# RS485.net
KiCad netlist of a schematic drawn in Altium Designer
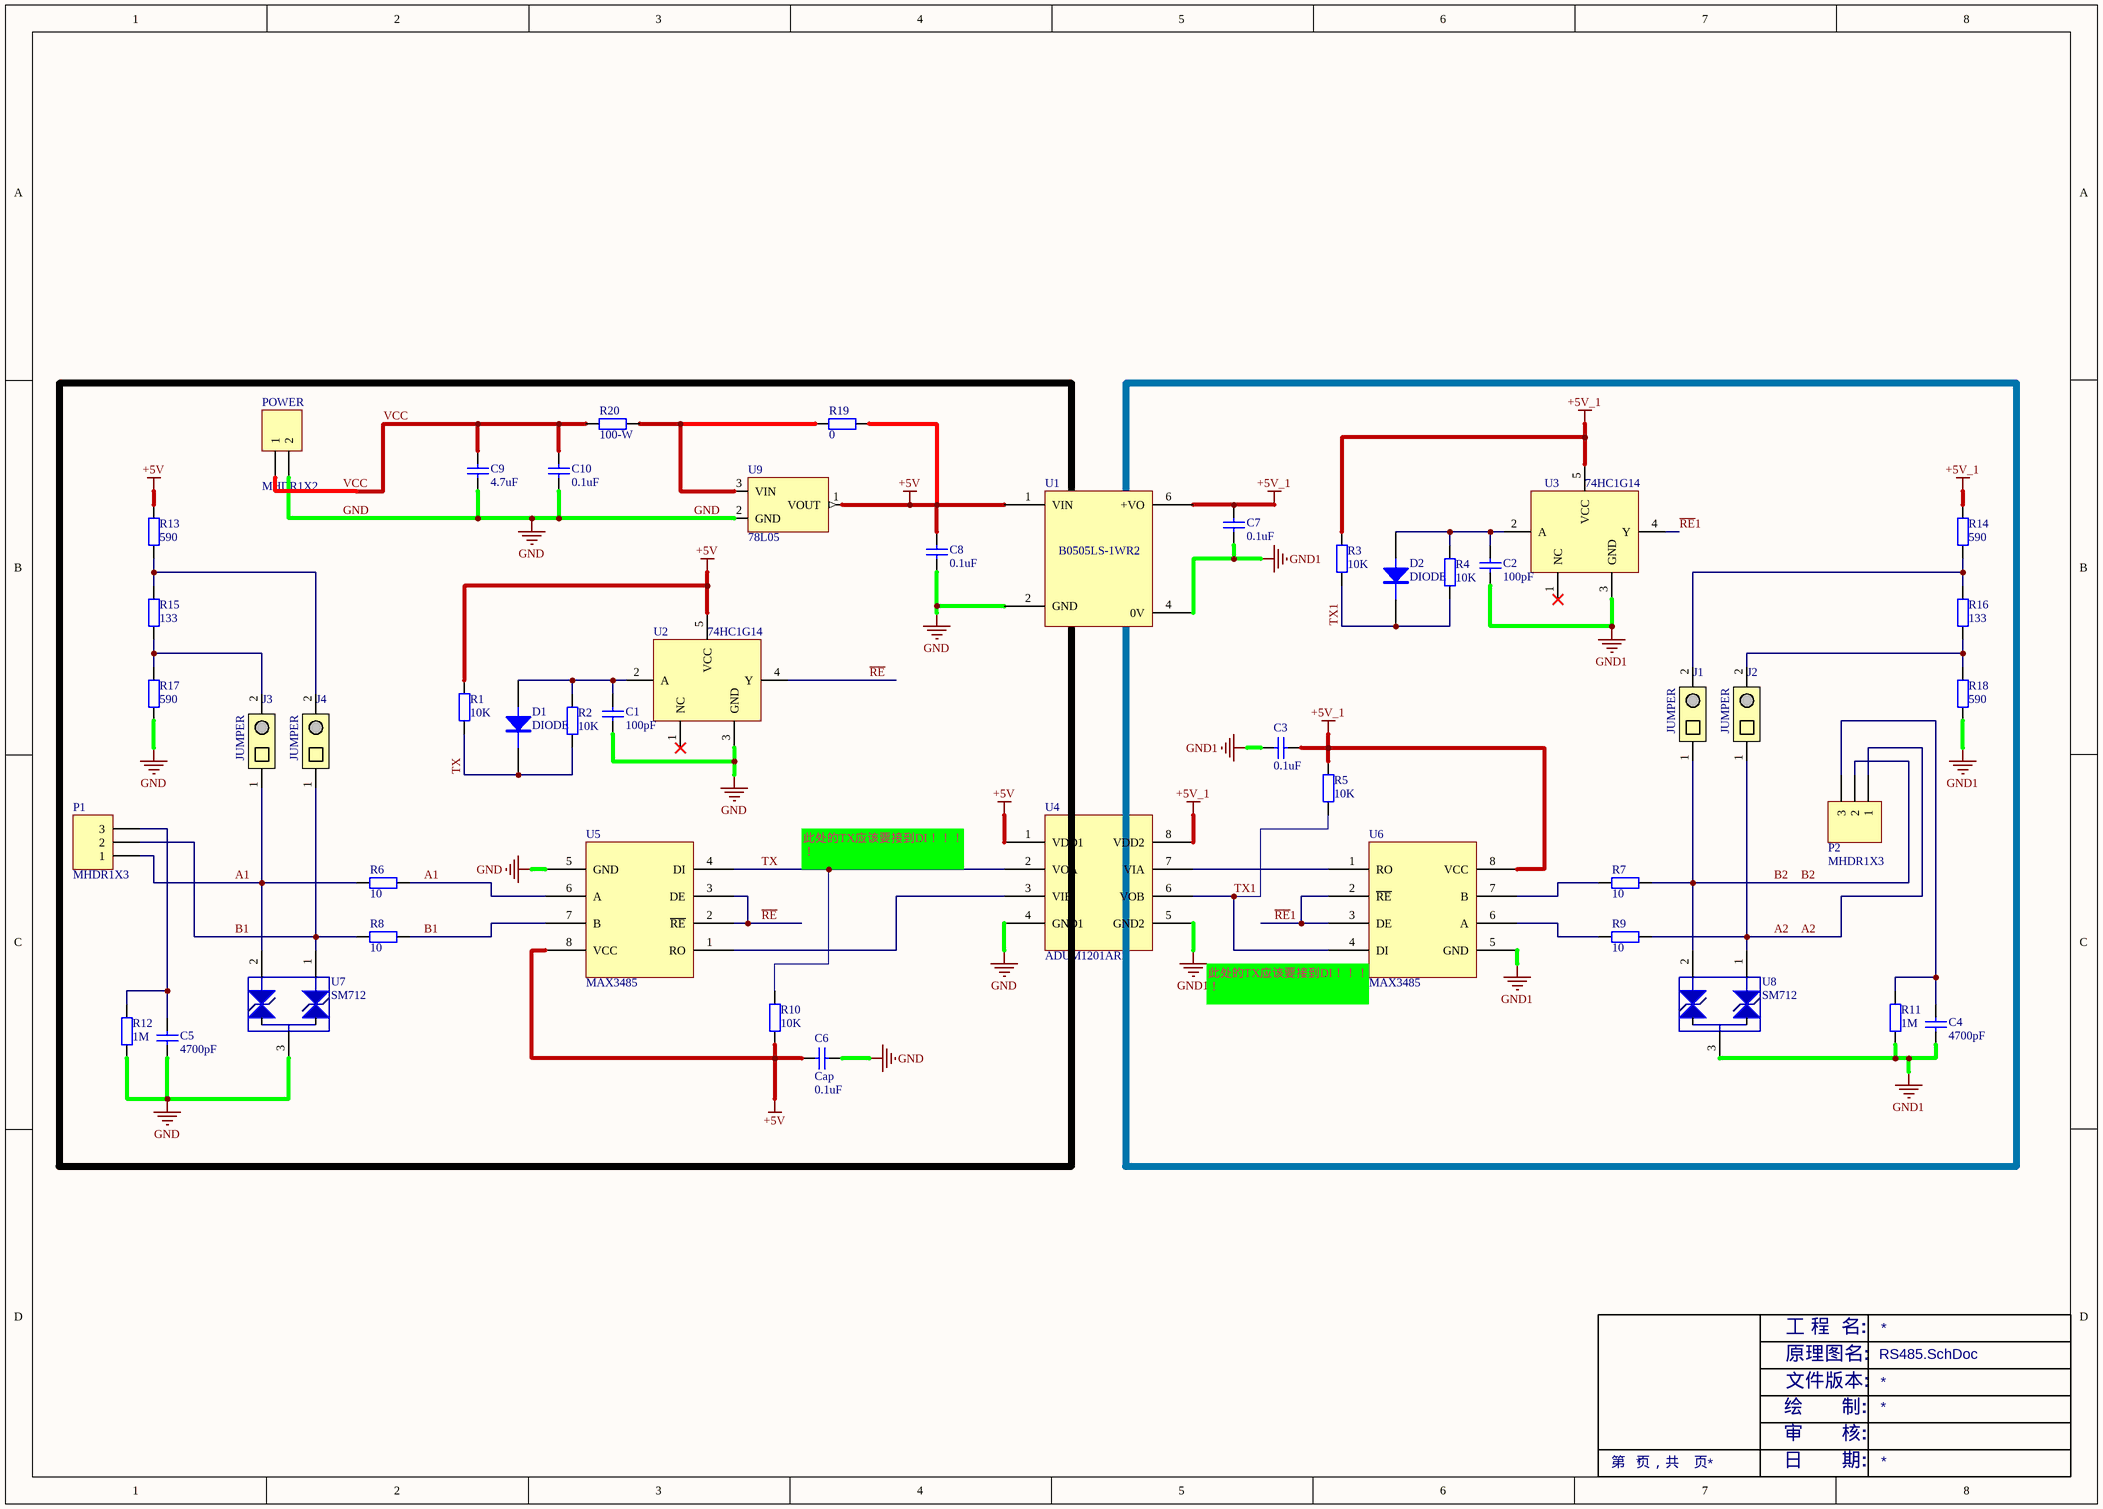
[diagram p0: RS485.SchDoc]

(export (version "E")
  (design (tool "Eeschema 10.0.6"))
  (components
    (comp (ref "C1")
      (value "100pF")
      (footprint "CC0603")
      (description "Capacitor")
      (fields (field (name "PUBLISHER") "Altium Limited"))
      (libsource (lib "Miscellaneous Devices") (part "Cap"))
    )
    (comp (ref "C2")
      (value "100pF")
      (footprint "CC0603")
      (description "Capacitor")
      (fields (field (name "PUBLISHER") "Altium Limited"))
      (libsource (lib "Miscellaneous Devices") (part "Cap"))
    )
    (comp (ref "C3")
      (value "0.1uF")
      (footprint "CC0603")
      (description "Capacitor")
      (fields (field (name "PUBLISHER") "Altium Limited"))
      (libsource (lib "Miscellaneous Devices") (part "Cap"))
    )
    (comp (ref "C4")
      (value "4700pF")
      (footprint "CC0603")
      (description "Capacitor")
      (fields (field (name "PUBLISHER") "Altium Limited"))
      (libsource (lib "Miscellaneous Devices") (part "Cap"))
    )
    (comp (ref "C5")
      (value "4700pF")
      (footprint "CC0603")
      (description "Capacitor")
      (fields (field (name "PUBLISHER") "Altium Limited"))
      (libsource (lib "Miscellaneous Devices") (part "Cap"))
    )
    (comp (ref "C6")
      (value "Cap")
      (footprint "CC0603")
      (description "Capacitor")
      (fields (field (name "ALTIUM_VALUE") "0.1uF") (field (name "PUBLISHER") "Altium Limited"))
      (libsource (lib "Miscellaneous Devices") (part "Cap"))
    )
    (comp (ref "C7")
      (value "0.1uF")
      (footprint "CC0603")
      (description "Capacitor")
      (fields (field (name "PUBLISHER") "Altium Limited"))
      (libsource (lib "Miscellaneous Devices") (part "Cap"))
    )
    (comp (ref "C8")
      (value "0.1uF")
      (footprint "CC0603")
      (description "Capacitor")
      (fields (field (name "PUBLISHER") "Altium Limited"))
      (libsource (lib "Miscellaneous Devices") (part "Cap"))
    )
    (comp (ref "C9")
      (value "4.7uF")
      (footprint "CC0603")
      (description "Capacitor")
      (fields (field (name "PUBLISHER") "Altium Limited"))
      (libsource (lib "Miscellaneous Devices") (part "Cap"))
    )
    (comp (ref "C10")
      (value "0.1uF")
      (footprint "CC0603")
      (description "Capacitor")
      (fields (field (name "PUBLISHER") "Altium Limited"))
      (libsource (lib "Miscellaneous Devices") (part "Cap"))
    )
    (comp (ref "D1") (value "DIODE") (footprint "SOD323") (libsource (lib "woylib2015") (part "DIODE")))
    (comp (ref "D2") (value "DIODE") (footprint "SOD323") (libsource (lib "woylib2015") (part "DIODE")))
    (comp (ref "J1") (value "JUMPER") (footprint "SIP2-2.54MM") (libsource (lib "Connector") (part "JUMPER")))
    (comp (ref "J2") (value "JUMPER") (footprint "SIP2-2.54MM") (libsource (lib "Connector") (part "JUMPER")))
    (comp (ref "J3") (value "JUMPER") (footprint "SIP2-2.54MM") (libsource (lib "Connector") (part "JUMPER")))
    (comp (ref "J4") (value "JUMPER") (footprint "SIP2-2.54MM") (libsource (lib "Connector") (part "JUMPER")))
    (comp (ref "P1")
      (value "MHDR1X3")
      (footprint "HEADER_35MM")
      (description "Header, 3-Pin")
      (fields (field (name "PUBLISHER") "Altium Limited"))
      (libsource (lib "Miscellaneous Connectors") (part "MHDR1X3"))
    )
    (comp (ref "P2")
      (value "MHDR1X3")
      (footprint "HEADER_35MM")
      (description "Header, 3-Pin")
      (fields (field (name "PUBLISHER") "Altium Limited"))
      (libsource (lib "") (part "MHDR1X3_1"))
    )
    (comp (ref "POWER")
      (value "MHDR1X2")
      (footprint "HEADER_35MM_2")
      (description "Header, 2-Pin")
      (fields (field (name "PUBLISHER") "Altium Limited"))
      (libsource (lib "Miscellaneous Connectors") (part "MHDR1X2"))
    )
    (comp (ref "R1")
      (value "10K")
      (footprint "CC0603")
      (description "Resistor")
      (fields (field (name "PUBLISHER") "Altium Limited"))
      (libsource (lib "Miscellaneous Devices") (part "Res2"))
    )
    (comp (ref "R2")
      (value "10K")
      (footprint "CC0603")
      (description "Resistor")
      (fields (field (name "PUBLISHER") "Altium Limited"))
      (libsource (lib "Miscellaneous Devices") (part "Res2"))
    )
    (comp (ref "R3")
      (value "10K")
      (footprint "CC0603")
      (description "Resistor")
      (fields (field (name "PUBLISHER") "Altium Limited"))
      (libsource (lib "Miscellaneous Devices") (part "Res2"))
    )
    (comp (ref "R4")
      (value "10K")
      (footprint "CC0603")
      (description "Resistor")
      (fields (field (name "PUBLISHER") "Altium Limited"))
      (libsource (lib "Miscellaneous Devices") (part "Res2"))
    )
    (comp (ref "R5")
      (value "10K")
      (footprint "CC0603")
      (description "Resistor")
      (fields (field (name "PUBLISHER") "Altium Limited"))
      (libsource (lib "Miscellaneous Devices") (part "Res2"))
    )
    (comp (ref "R6")
      (value "10")
      (footprint "CC0603")
      (description "Resistor")
      (fields (field (name "PUBLISHER") "Altium Limited"))
      (libsource (lib "") (part "Res2_3"))
    )
    (comp (ref "R7")
      (value "10")
      (footprint "CC0603")
      (description "Resistor")
      (fields (field (name "PUBLISHER") "Altium Limited"))
      (libsource (lib "") (part "Res2_1"))
    )
    (comp (ref "R8")
      (value "10")
      (footprint "CC0603")
      (description "Resistor")
      (fields (field (name "PUBLISHER") "Altium Limited"))
      (libsource (lib "") (part "Res2_3"))
    )
    (comp (ref "R9")
      (value "10")
      (footprint "CC0603")
      (description "Resistor")
      (fields (field (name "PUBLISHER") "Altium Limited"))
      (libsource (lib "") (part "Res2_1"))
    )
    (comp (ref "R10")
      (value "10K")
      (footprint "CC0603")
      (description "Resistor")
      (fields (field (name "PUBLISHER") "Altium Limited"))
      (libsource (lib "") (part "Res2_2"))
    )
    (comp (ref "R11")
      (value "1M")
      (footprint "CC0603")
      (description "Resistor")
      (fields (field (name "PUBLISHER") "Altium Limited"))
      (libsource (lib "") (part "Res2_2"))
    )
    (comp (ref "R12")
      (value "1M")
      (footprint "CC0603")
      (description "Resistor")
      (fields (field (name "PUBLISHER") "Altium Limited"))
      (libsource (lib "") (part "Res2_2"))
    )
    (comp (ref "R13")
      (value "590")
      (footprint "CC0603")
      (description "Resistor")
      (fields (field (name "PUBLISHER") "Altium Limited"))
      (libsource (lib "Miscellaneous Devices") (part "Res2"))
    )
    (comp (ref "R14")
      (value "590")
      (footprint "CC0603")
      (description "Resistor")
      (fields (field (name "PUBLISHER") "Altium Limited"))
      (libsource (lib "Miscellaneous Devices") (part "Res2"))
    )
    (comp (ref "R15")
      (value "133")
      (footprint "CC0603")
      (description "Resistor")
      (fields (field (name "PUBLISHER") "Altium Limited"))
      (libsource (lib "Miscellaneous Devices") (part "Res2"))
    )
    (comp (ref "R16")
      (value "133")
      (footprint "CC0603")
      (description "Resistor")
      (fields (field (name "PUBLISHER") "Altium Limited"))
      (libsource (lib "Miscellaneous Devices") (part "Res2"))
    )
    (comp (ref "R17")
      (value "590")
      (footprint "CC0603")
      (description "Resistor")
      (fields (field (name "PUBLISHER") "Altium Limited"))
      (libsource (lib "Miscellaneous Devices") (part "Res2"))
    )
    (comp (ref "R18")
      (value "590")
      (footprint "CC0603")
      (description "Resistor")
      (fields (field (name "PUBLISHER") "Altium Limited"))
      (libsource (lib "Miscellaneous Devices") (part "Res2"))
    )
    (comp (ref "R19")
      (value "0")
      (footprint "CC0603")
      (description "Resistor")
      (fields (field (name "PUBLISHER") "Altium Limited"))
      (libsource (lib "") (part "Res2_1"))
    )
    (comp (ref "R20")
      (value "100-W")
      (footprint "AXIAL-0.3")
      (description "Resistor")
      (fields (field (name "PUBLISHER") "Altium Limited"))
      (libsource (lib "") (part "Res2_1"))
    )
    (comp (ref "U1")
      (value "B0505LS-1WR2")
      (footprint "B0505LS-1WR2")
      (libsource (lib "IC") (part "B0505LS-1WR2"))
    )
    (comp (ref "U2")
      (value "74HC1G14")
      (footprint "SOT-23-5")
      (libsource (lib "woylib2015") (part "74HC1G14"))
    )
    (comp (ref "U3")
      (value "74HC1G14")
      (footprint "SOT-23-5")
      (libsource (lib "woylib2015") (part "74HC1G14"))
    )
    (comp (ref "U4")
      (value "ADUM1201ARZ")
      (footprint "SO-8")
      (libsource (lib "woylib2015") (part "ADUM1201ARZ"))
    )
    (comp (ref "U5") (value "MAX3485") (footprint "SO-8") (libsource (lib "") (part "MAX3485_1")))
    (comp (ref "U6") (value "MAX3485") (footprint "SO-8") (libsource (lib "woylib2015") (part "MAX3485")))
    (comp (ref "U7") (value "SM712") (footprint "SOT-23W") (libsource (lib "woylib2015") (part "SM712")))
    (comp (ref "U8") (value "SM712") (footprint "SOT-23W") (libsource (lib "woylib2015") (part "SM712")))
    (comp (ref "U9")
      (value "78L05")
      (footprint "SOT-89")
      (description "CI-78L05")
      (libsource (lib "woylib2015") (part "78L05"))
    )
  )
  (nets
    (net (code "1") (name "+5V") (class "Default")
      (node (ref "C6") (pin "1") (pinfunction "1_1") (pintype "passive"))
      (node (ref "C8") (pin "1") (pinfunction "1_1") (pintype "passive"))
      (node (ref "R1") (pin "2") (pinfunction "2_2") (pintype "passive"))
      (node (ref "R10") (pin "2") (pinfunction "2_2") (pintype "passive"))
      (node (ref "R13") (pin "2") (pinfunction "2_2") (pintype "passive"))
      (node (ref "R19") (pin "1") (pinfunction "1_1") (pintype "passive"))
      (node (ref "U1") (pin "1") (pinfunction "VIN_1") (pintype "passive"))
      (node (ref "U2") (pin "5") (pinfunction "VCC_5") (pintype "passive"))
      (node (ref "U4") (pin "1") (pinfunction "VDD1_1") (pintype "passive"))
      (node (ref "U5") (pin "8") (pinfunction "VCC_8") (pintype "passive"))
      (node (ref "U9") (pin "1") (pinfunction "VOUT_1") (pintype "output"))
    )
    (net (code "2") (name "+5V_1") (class "Default")
      (node (ref "C3") (pin "1") (pinfunction "1_1") (pintype "passive"))
      (node (ref "C7") (pin "1") (pinfunction "1_1") (pintype "passive"))
      (node (ref "R14") (pin "2") (pinfunction "2_2") (pintype "passive"))
      (node (ref "R3") (pin "2") (pinfunction "2_2") (pintype "passive"))
      (node (ref "R5") (pin "2") (pinfunction "2_2") (pintype "passive"))
      (node (ref "U1") (pin "6") (pinfunction "+VO_6") (pintype "passive"))
      (node (ref "U3") (pin "5") (pinfunction "VCC_5") (pintype "passive"))
      (node (ref "U4") (pin "8") (pinfunction "VDD2_8") (pintype "passive"))
      (node (ref "U6") (pin "8") (pinfunction "VCC_8") (pintype "passive"))
    )
    (net (code "3") (name "/A1") (class "Default")
      (node (ref "J3") (pin "1") (pinfunction "1_1") (pintype "passive"))
      (node (ref "P1") (pin "1") (pinfunction "1_1") (pintype "passive"))
      (node (ref "R6") (pin "1") (pinfunction "1_1") (pintype "passive"))
      (node (ref "R6") (pin "2") (pinfunction "2_2") (pintype "passive"))
      (node (ref "U5") (pin "6") (pinfunction "A_6") (pintype "passive"))
      (node (ref "U7") (pin "2") (pinfunction "2_2") (pintype "passive"))
    )
    (net (code "4") (name "/A2") (class "Default")
      (node (ref "J2") (pin "1") (pinfunction "1_1") (pintype "passive"))
      (node (ref "P2") (pin "1") (pinfunction "1_1") (pintype "passive"))
      (node (ref "R9") (pin "1") (pinfunction "1_1") (pintype "passive"))
      (node (ref "U8") (pin "1") (pinfunction "1_1") (pintype "passive"))
    )
    (net (code "5") (name "/B1") (class "Default")
      (node (ref "J4") (pin "1") (pinfunction "1_1") (pintype "passive"))
      (node (ref "P1") (pin "2") (pinfunction "2_2") (pintype "passive"))
      (node (ref "R8") (pin "1") (pinfunction "1_1") (pintype "passive"))
      (node (ref "R8") (pin "2") (pinfunction "2_2") (pintype "passive"))
      (node (ref "U5") (pin "7") (pinfunction "B_7") (pintype "passive"))
      (node (ref "U7") (pin "1") (pinfunction "1_1") (pintype "passive"))
    )
    (net (code "6") (name "/B2") (class "Default")
      (node (ref "J1") (pin "1") (pinfunction "1_1") (pintype "passive"))
      (node (ref "P2") (pin "2") (pinfunction "2_2") (pintype "passive"))
      (node (ref "R7") (pin "1") (pinfunction "1_1") (pintype "passive"))
      (node (ref "U8") (pin "2") (pinfunction "2_2") (pintype "passive"))
    )
    (net (code "7") (name "/TX") (class "Default")
      (node (ref "D1") (pin "2") (pinfunction "K_2") (pintype "passive"))
      (node (ref "R1") (pin "1") (pinfunction "1_1") (pintype "passive"))
      (node (ref "R10") (pin "1") (pinfunction "1_1") (pintype "passive"))
      (node (ref "R2") (pin "1") (pinfunction "1_1") (pintype "passive"))
      (node (ref "U4") (pin "2") (pinfunction "VOA_2") (pintype "passive"))
      (node (ref "U5") (pin "4") (pinfunction "DI_4") (pintype "passive"))
    )
    (net (code "8") (name "/TX1") (class "Default")
      (node (ref "D2") (pin "2") (pinfunction "K_2") (pintype "passive"))
      (node (ref "R3") (pin "1") (pinfunction "1_1") (pintype "passive"))
      (node (ref "R4") (pin "1") (pinfunction "1_1") (pintype "passive"))
      (node (ref "R5") (pin "1") (pinfunction "1_1") (pintype "passive"))
      (node (ref "U4") (pin "6") (pinfunction "VOB_6") (pintype "passive"))
      (node (ref "U6") (pin "4") (pinfunction "DI_4") (pintype "passive"))
    )
    (net (code "9") (name "/VCC") (class "Default")
      (node (ref "C10") (pin "1") (pinfunction "1_1") (pintype "passive"))
      (node (ref "C9") (pin "1") (pinfunction "1_1") (pintype "passive"))
      (node (ref "POWER") (pin "1") (pinfunction "1_1") (pintype "passive"))
      (node (ref "R20") (pin "2") (pinfunction "2_2") (pintype "passive"))
    )
    (net (code "10") (name "/~{RE}") (class "Default")
      (node (ref "U2") (pin "4") (pinfunction "Y_4") (pintype "passive"))
      (node (ref "U5") (pin "2") (pinfunction "~{RE}_2") (pintype "passive"))
      (node (ref "U5") (pin "3") (pinfunction "DE_3") (pintype "passive"))
    )
    (net (code "11") (name "/~{RE}1") (class "Default")
      (node (ref "U3") (pin "4") (pinfunction "Y_4") (pintype "passive"))
      (node (ref "U6") (pin "2") (pinfunction "~{RE}_2") (pintype "passive"))
      (node (ref "U6") (pin "3") (pinfunction "DE_3") (pintype "passive"))
    )
    (net (code "12") (name "GND") (class "Default")
      (node (ref "C1") (pin "1") (pinfunction "1_1") (pintype "passive"))
      (node (ref "C10") (pin "2") (pinfunction "2_2") (pintype "passive"))
      (node (ref "C5") (pin "1") (pinfunction "1_1") (pintype "passive"))
      (node (ref "C6") (pin "2") (pinfunction "2_2") (pintype "passive"))
      (node (ref "C8") (pin "2") (pinfunction "2_2") (pintype "passive"))
      (node (ref "C9") (pin "2") (pinfunction "2_2") (pintype "passive"))
      (node (ref "POWER") (pin "2") (pinfunction "2_2") (pintype "passive"))
      (node (ref "R12") (pin "2") (pinfunction "2_2") (pintype "passive"))
      (node (ref "R17") (pin "1") (pinfunction "1_1") (pintype "passive"))
      (node (ref "U1") (pin "2") (pinfunction "GND_2") (pintype "passive"))
      (node (ref "U2") (pin "3") (pinfunction "GND_3") (pintype "passive"))
      (node (ref "U4") (pin "4") (pinfunction "GND1_4") (pintype "passive"))
      (node (ref "U5") (pin "5") (pinfunction "GND_5") (pintype "passive"))
      (node (ref "U7") (pin "3") (pinfunction "3_3") (pintype "passive"))
      (node (ref "U9") (pin "2") (pinfunction "GND_2") (pintype "power_in"))
    )
    (net (code "13") (name "GND1") (class "Default")
      (node (ref "C2") (pin "1") (pinfunction "1_1") (pintype "passive"))
      (node (ref "C3") (pin "2") (pinfunction "2_2") (pintype "passive"))
      (node (ref "C4") (pin "1") (pinfunction "1_1") (pintype "passive"))
      (node (ref "C7") (pin "2") (pinfunction "2_2") (pintype "passive"))
      (node (ref "R11") (pin "2") (pinfunction "2_2") (pintype "passive"))
      (node (ref "R18") (pin "1") (pinfunction "1_1") (pintype "passive"))
      (node (ref "U1") (pin "4") (pinfunction "0V_4") (pintype "passive"))
      (node (ref "U3") (pin "3") (pinfunction "GND_3") (pintype "passive"))
      (node (ref "U4") (pin "5") (pinfunction "GND2_5") (pintype "passive"))
      (node (ref "U6") (pin "5") (pinfunction "GND_5") (pintype "passive"))
      (node (ref "U8") (pin "3") (pinfunction "3_3") (pintype "passive"))
    )
    (net (code "14") (name "Net-(C4-Pad2)") (class "Default")
      (node (ref "C4") (pin "2") (pinfunction "2_2") (pintype "passive"))
      (node (ref "P2") (pin "3") (pinfunction "3_3") (pintype "passive"))
      (node (ref "R11") (pin "1") (pinfunction "1_1") (pintype "passive"))
    )
    (net (code "15") (name "Net-(C5-Pad2)") (class "Default")
      (node (ref "C5") (pin "2") (pinfunction "2_2") (pintype "passive"))
      (node (ref "P1") (pin "3") (pinfunction "3_3") (pintype "passive"))
      (node (ref "R12") (pin "1") (pinfunction "1_1") (pintype "passive"))
    )
    (net (code "16") (name "Net-(D1-A)") (class "Default")
      (node (ref "C1") (pin "2") (pinfunction "2_2") (pintype "passive"))
      (node (ref "D1") (pin "1") (pinfunction "A_1") (pintype "passive"))
      (node (ref "R2") (pin "2") (pinfunction "2_2") (pintype "passive"))
      (node (ref "U2") (pin "2") (pinfunction "A_2") (pintype "passive"))
    )
    (net (code "17") (name "Net-(D2-A)") (class "Default")
      (node (ref "C2") (pin "2") (pinfunction "2_2") (pintype "passive"))
      (node (ref "D2") (pin "1") (pinfunction "A_1") (pintype "passive"))
      (node (ref "R4") (pin "2") (pinfunction "2_2") (pintype "passive"))
      (node (ref "U3") (pin "2") (pinfunction "A_2") (pintype "passive"))
    )
    (net (code "18") (name "Net-(J1-Pad2)") (class "Default")
      (node (ref "J1") (pin "2") (pinfunction "2_2") (pintype "passive"))
      (node (ref "R14") (pin "1") (pinfunction "1_1") (pintype "passive"))
      (node (ref "R16") (pin "2") (pinfunction "2_2") (pintype "passive"))
    )
    (net (code "19") (name "Net-(J2-Pad2)") (class "Default")
      (node (ref "J2") (pin "2") (pinfunction "2_2") (pintype "passive"))
      (node (ref "R16") (pin "1") (pinfunction "1_1") (pintype "passive"))
      (node (ref "R18") (pin "2") (pinfunction "2_2") (pintype "passive"))
    )
    (net (code "20") (name "Net-(J3-Pad2)") (class "Default")
      (node (ref "J3") (pin "2") (pinfunction "2_2") (pintype "passive"))
      (node (ref "R15") (pin "1") (pinfunction "1_1") (pintype "passive"))
      (node (ref "R17") (pin "2") (pinfunction "2_2") (pintype "passive"))
    )
    (net (code "21") (name "Net-(J4-Pad2)") (class "Default")
      (node (ref "J4") (pin "2") (pinfunction "2_2") (pintype "passive"))
      (node (ref "R13") (pin "1") (pinfunction "1_1") (pintype "passive"))
      (node (ref "R15") (pin "2") (pinfunction "2_2") (pintype "passive"))
    )
    (net (code "22") (name "Net-(U4-VIA)") (class "Default")
      (node (ref "U4") (pin "7") (pinfunction "VIA_7") (pintype "passive"))
      (node (ref "U6") (pin "1") (pinfunction "RO_1") (pintype "passive"))
    )
    (net (code "23") (name "Net-(U4-VIB)") (class "Default")
      (node (ref "U4") (pin "3") (pinfunction "VIB_3") (pintype "passive"))
      (node (ref "U5") (pin "1") (pinfunction "RO_1") (pintype "passive"))
    )
    (net (code "24") (name "Net-(U6-A)") (class "Default")
      (node (ref "R9") (pin "2") (pinfunction "2_2") (pintype "passive"))
      (node (ref "U6") (pin "6") (pinfunction "A_6") (pintype "passive"))
    )
    (net (code "25") (name "Net-(U6-B)") (class "Default")
      (node (ref "R7") (pin "2") (pinfunction "2_2") (pintype "passive"))
      (node (ref "U6") (pin "7") (pinfunction "B_7") (pintype "passive"))
    )
    (net (code "26") (name "Net-(U9-VIN)") (class "Default")
      (node (ref "R19") (pin "2") (pinfunction "2_2") (pintype "passive"))
      (node (ref "R20") (pin "1") (pinfunction "1_1") (pintype "passive"))
      (node (ref "U9") (pin "3") (pinfunction "VIN_3") (pintype "power_in"))
    )
    (net (code "27") (name "unconnected-(U2-NC-Pad1)") (class "Default")
      (node (ref "U2") (pin "1") (pinfunction "NC_1") (pintype "passive+no_connect"))
    )
    (net (code "28") (name "unconnected-(U3-NC-Pad1)") (class "Default")
      (node (ref "U3") (pin "1") (pinfunction "NC_1") (pintype "passive+no_connect"))
    )
  )
)
